# Dronmarket_Controller.net
KiCad netlist of a schematic drawn in EasyEDA
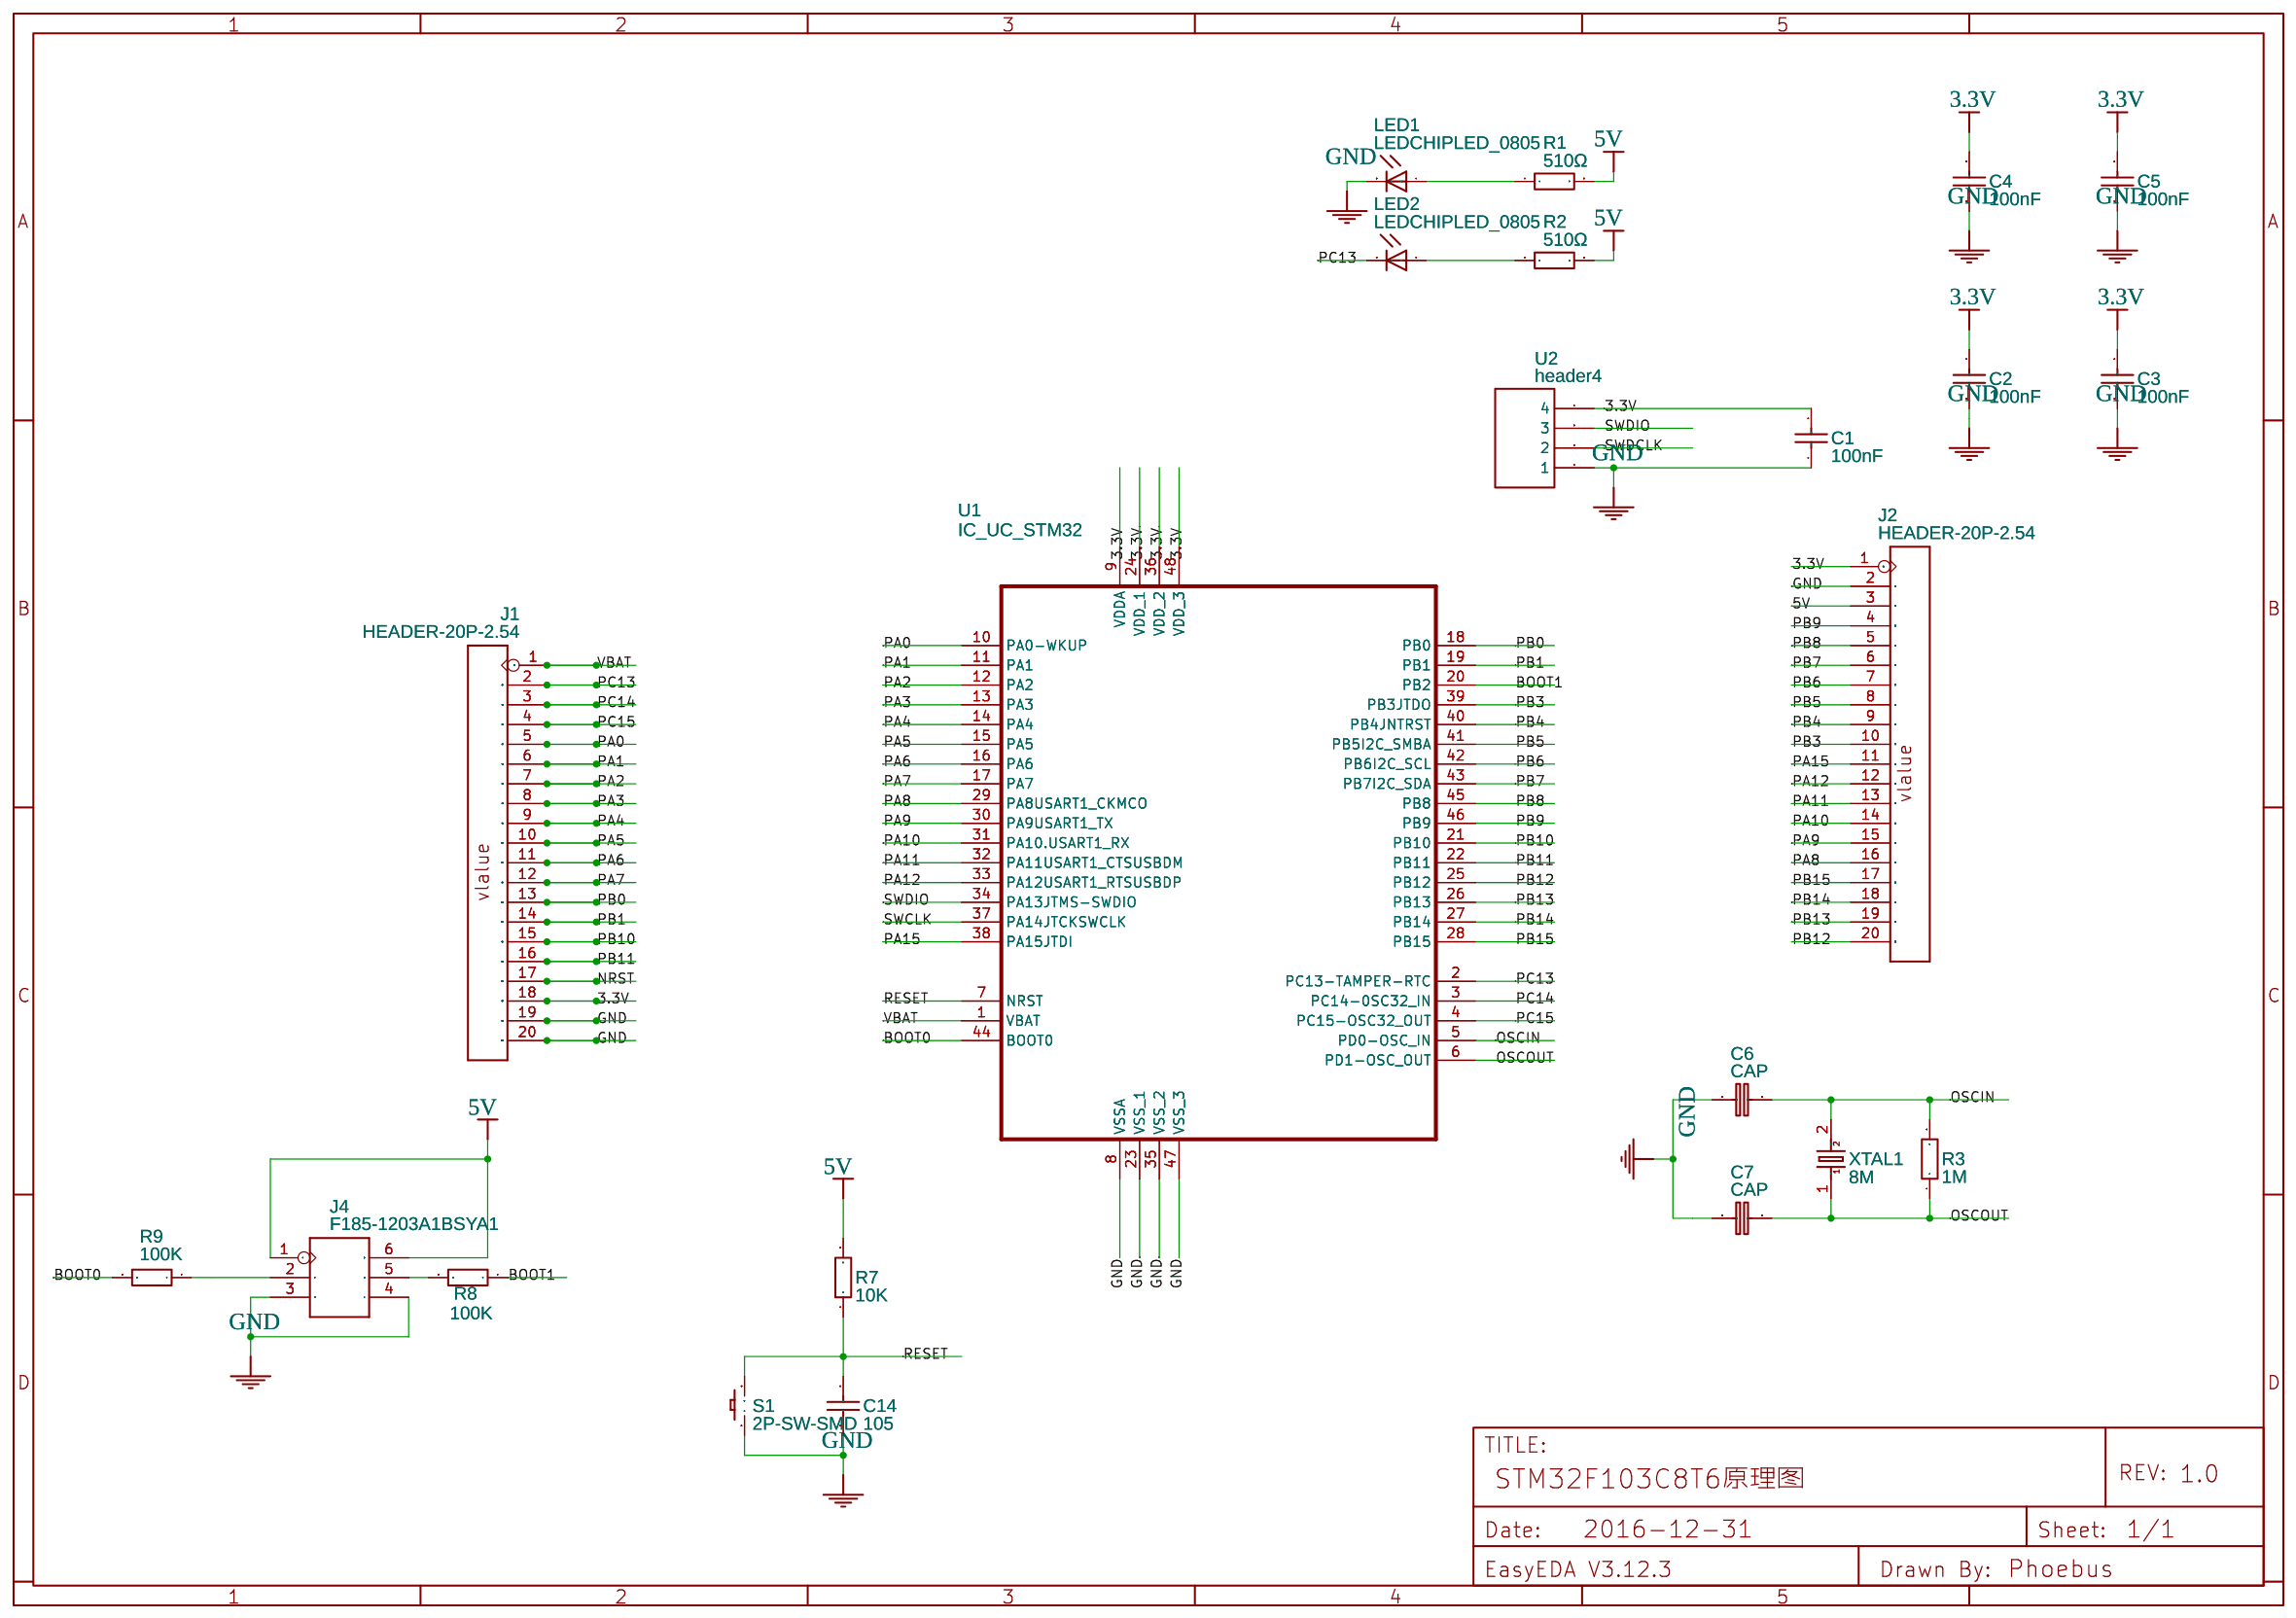
[diagram p0: Cpu Sheet]
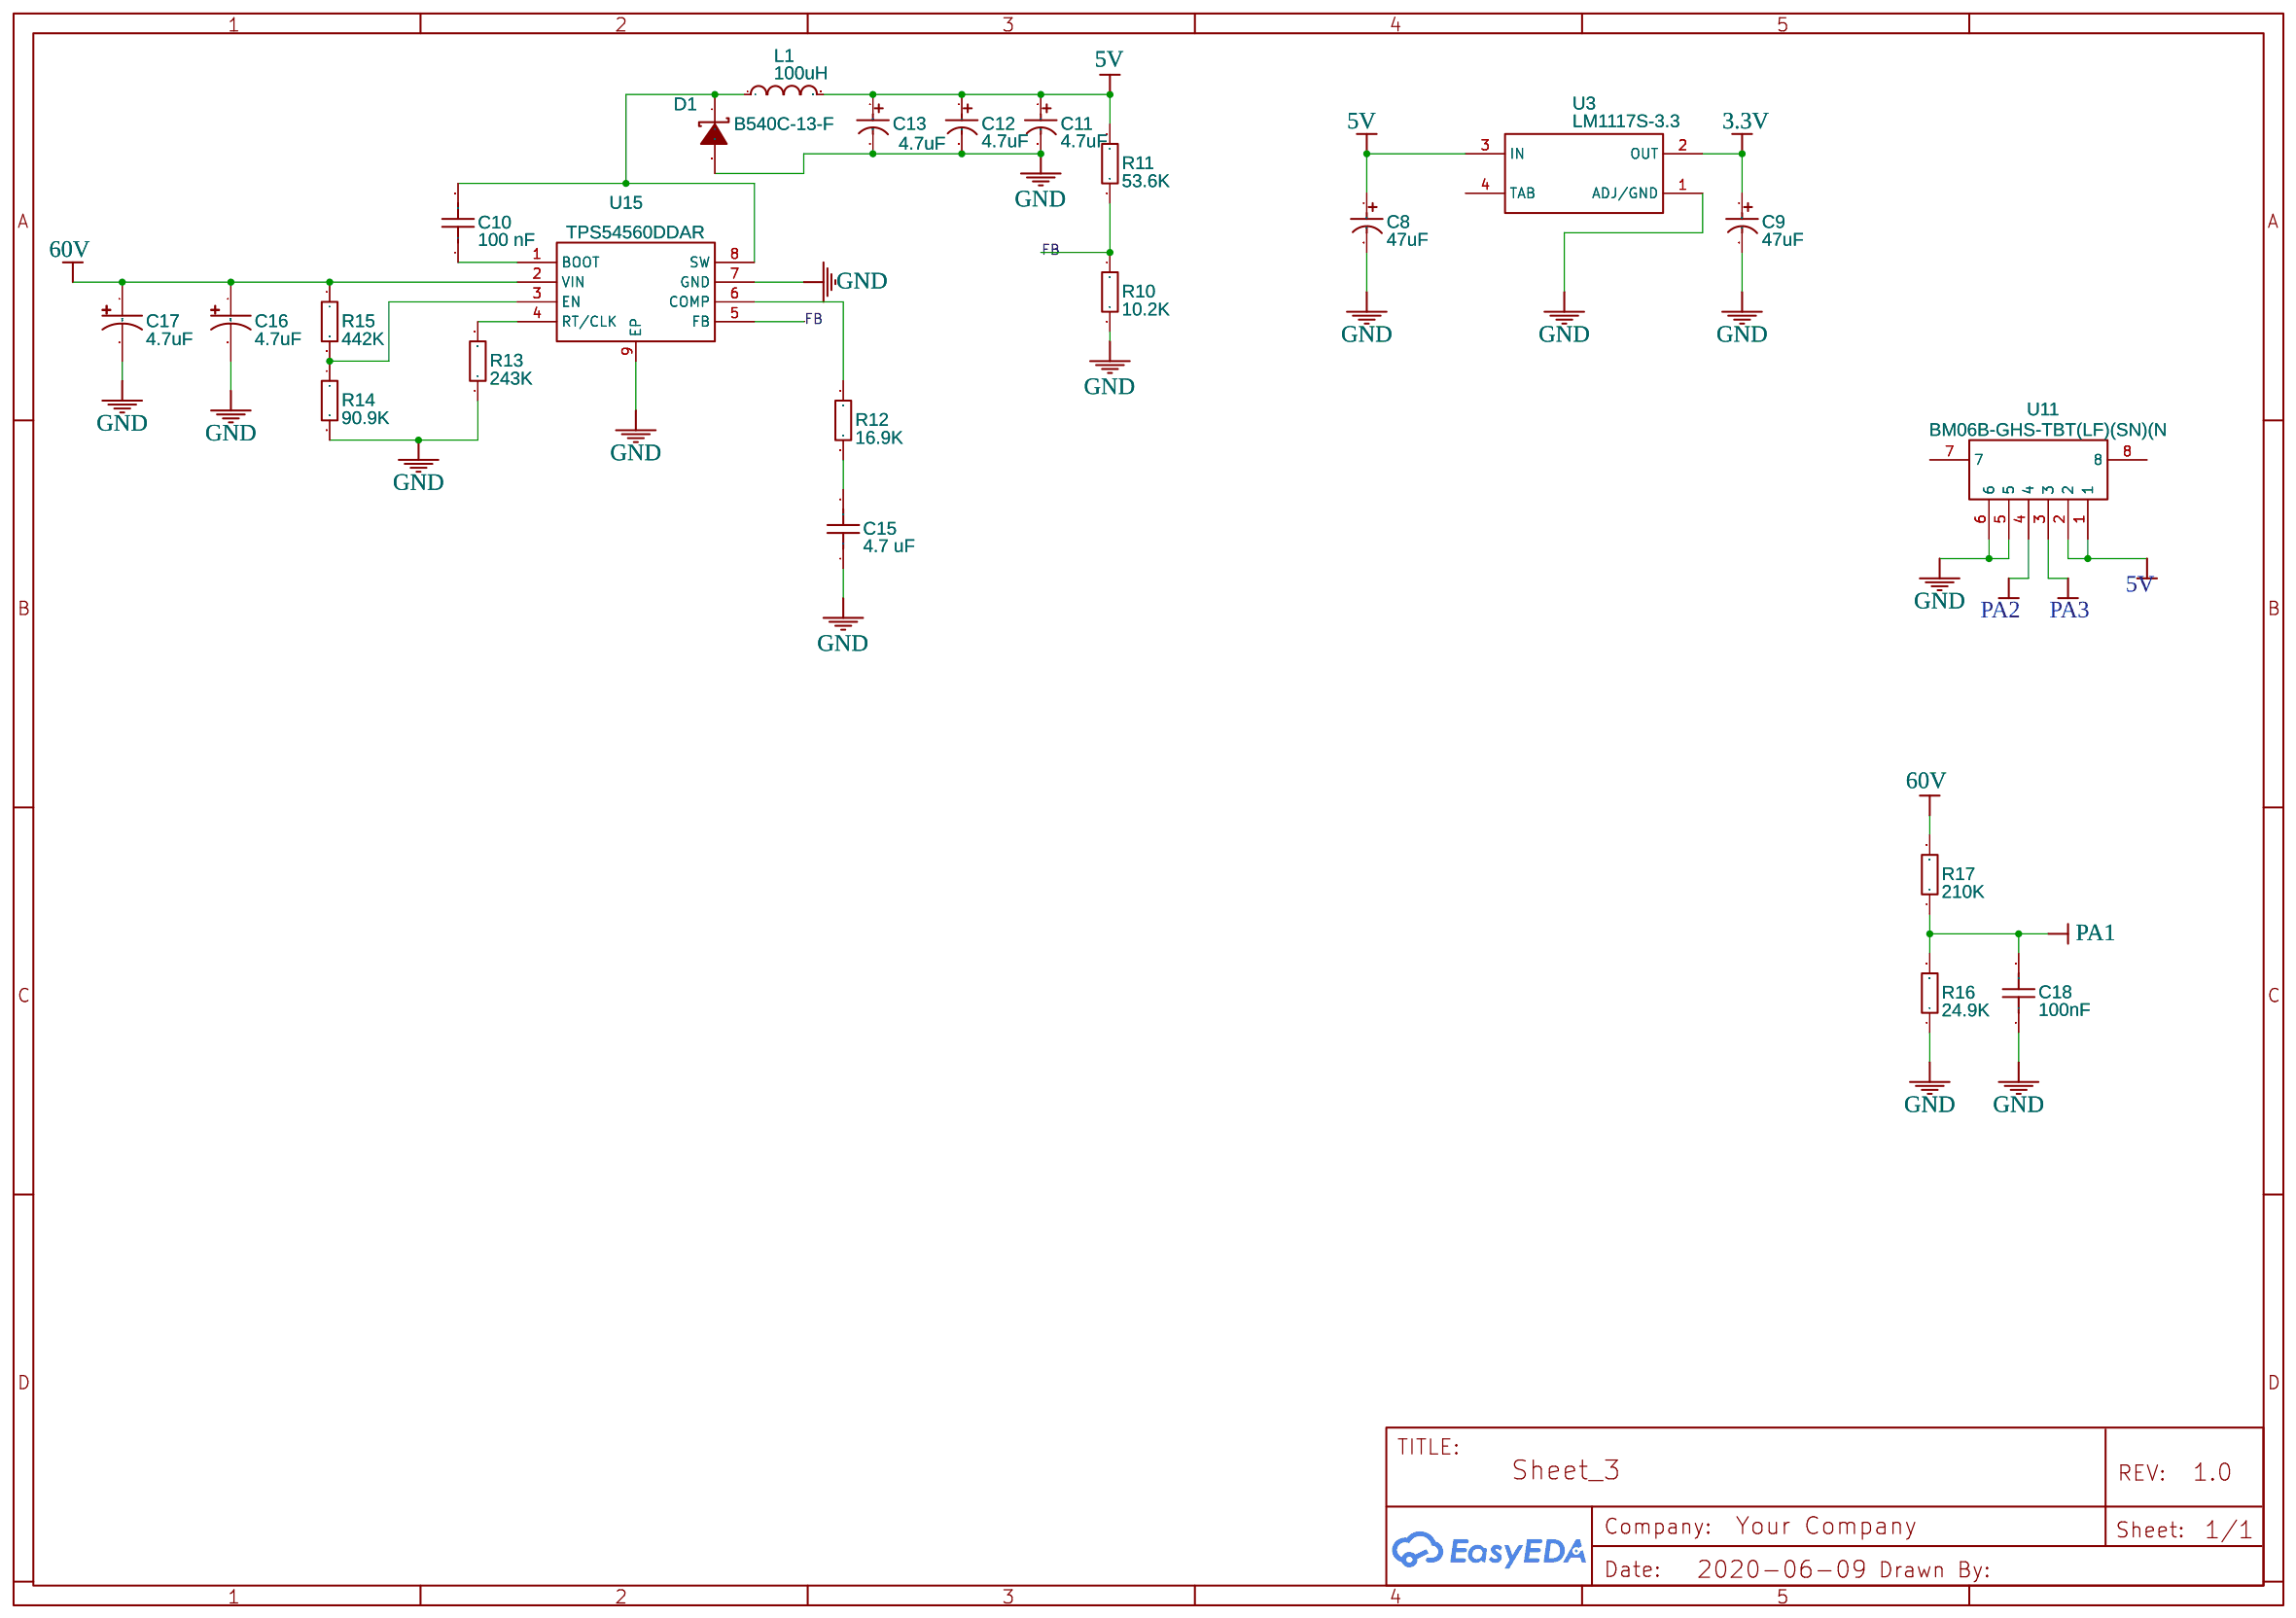
[diagram p1: Power Sheet]
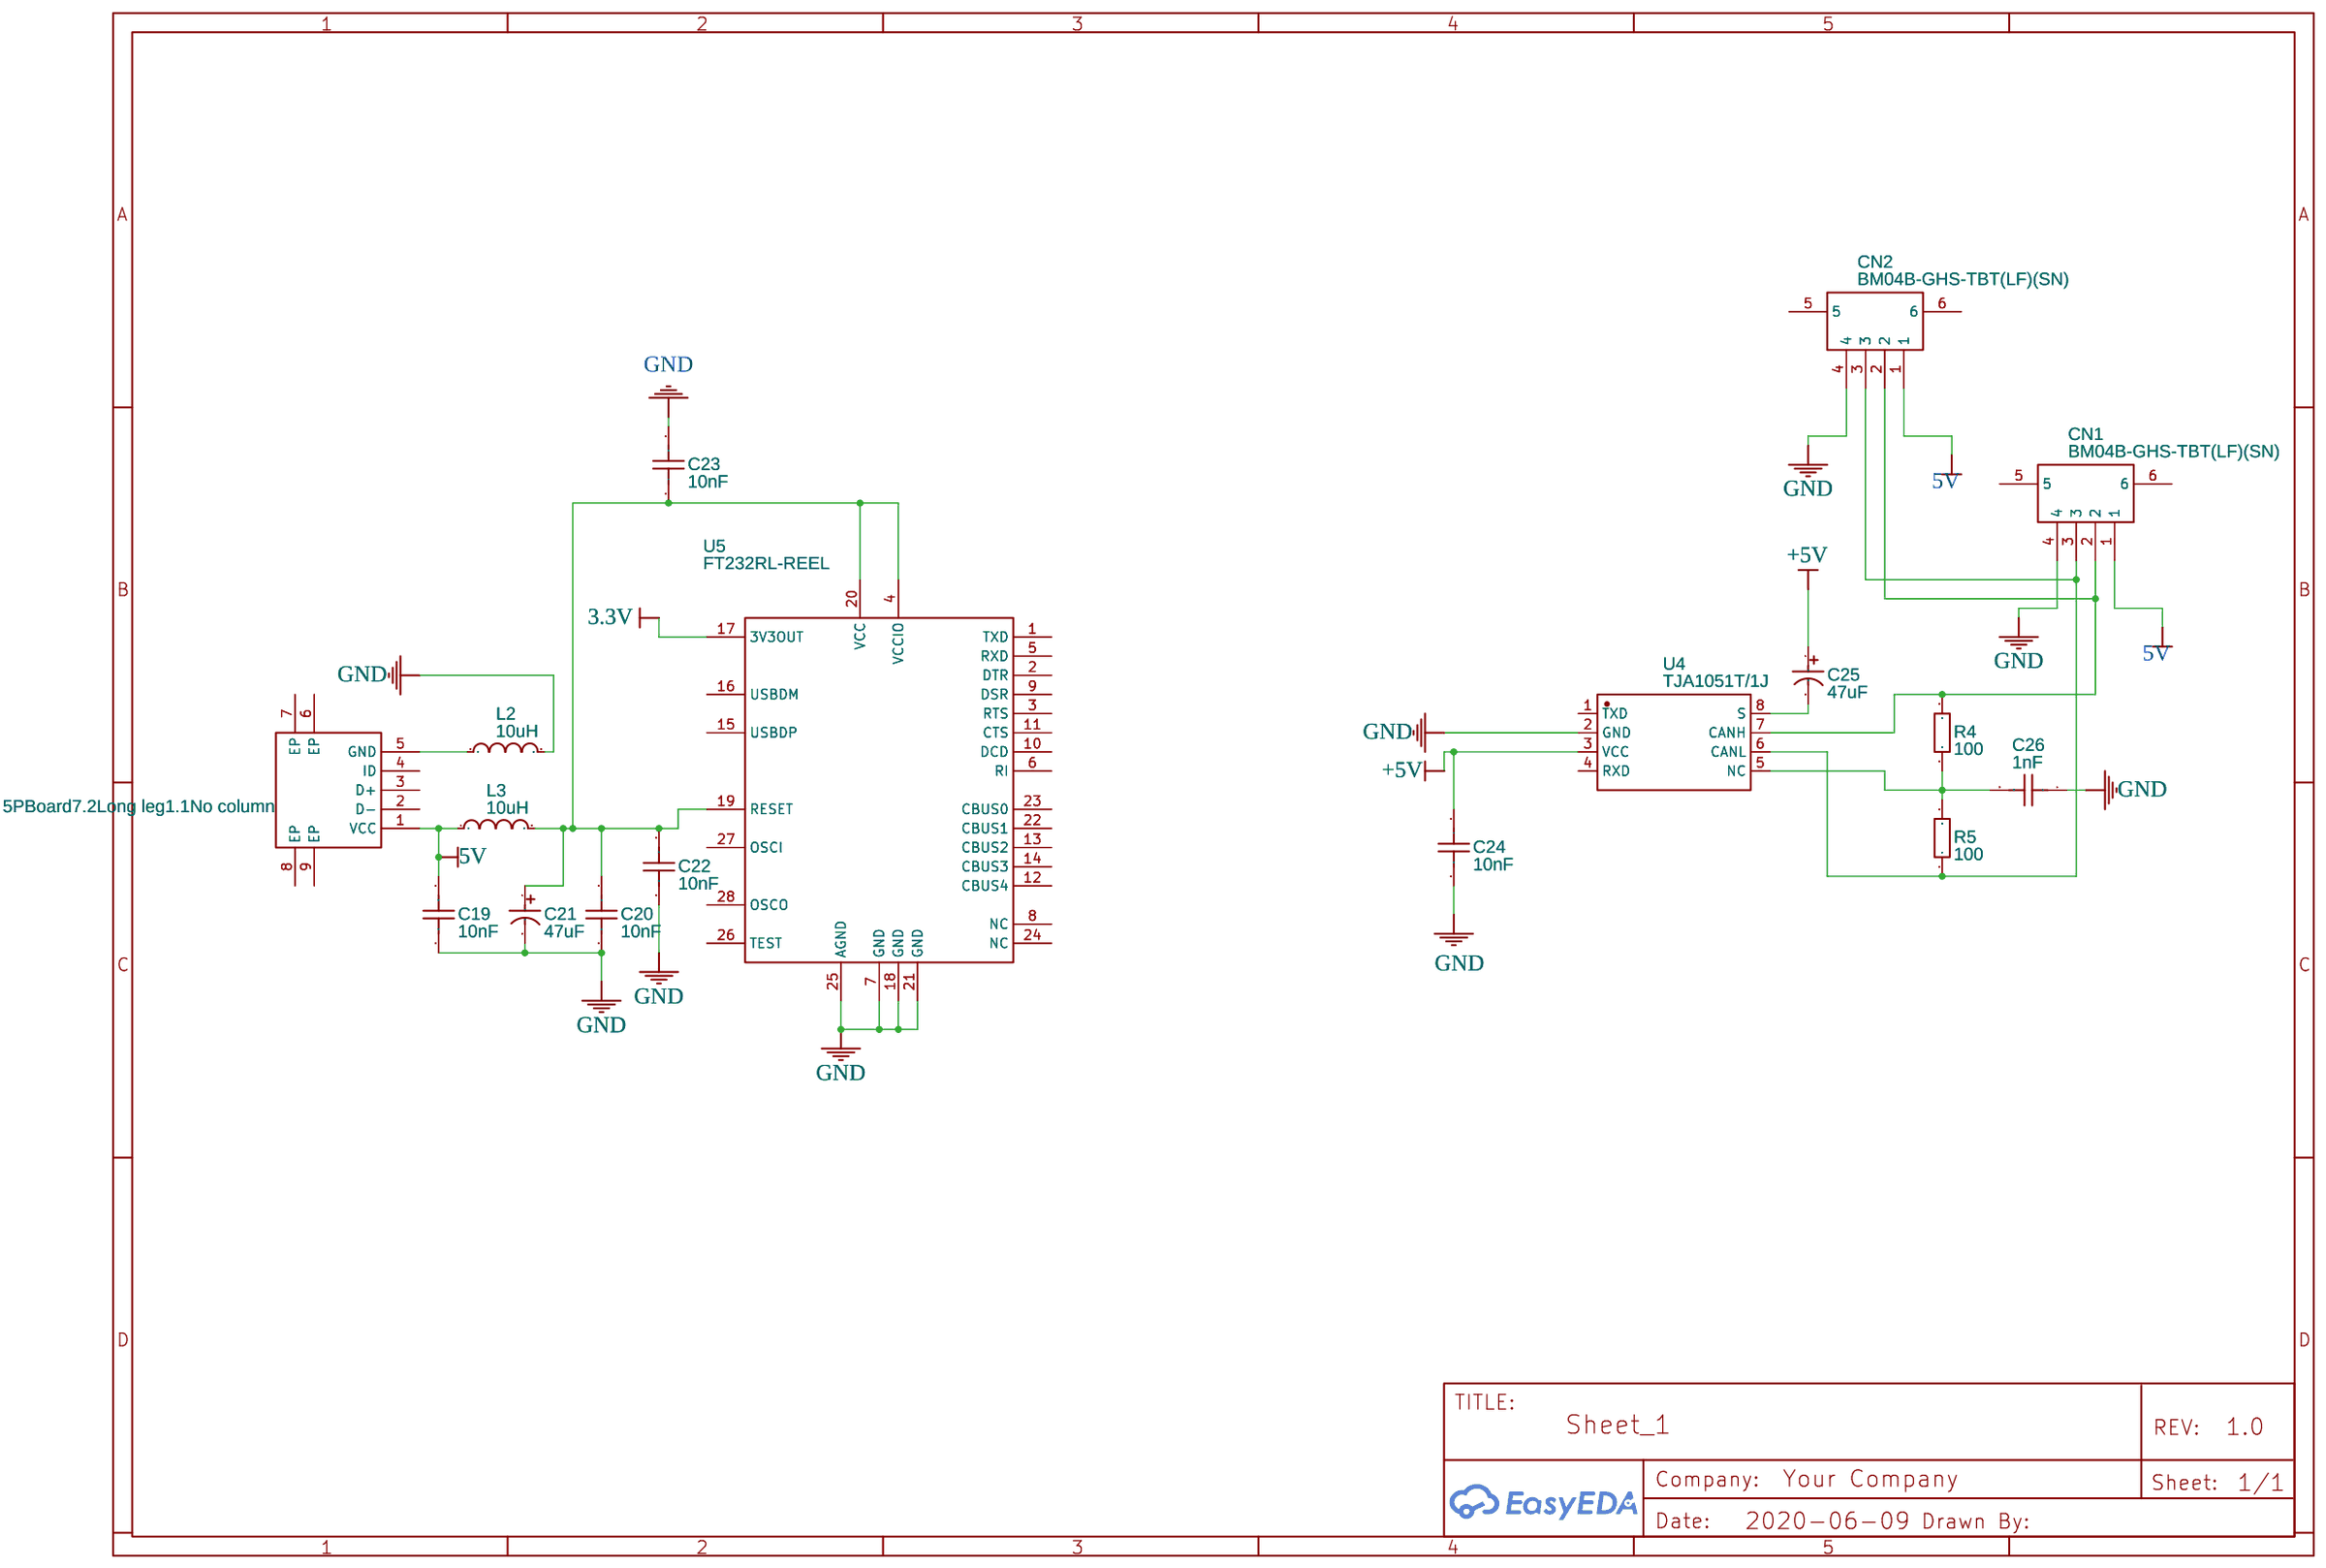
[diagram p2: Comminication Sheet]
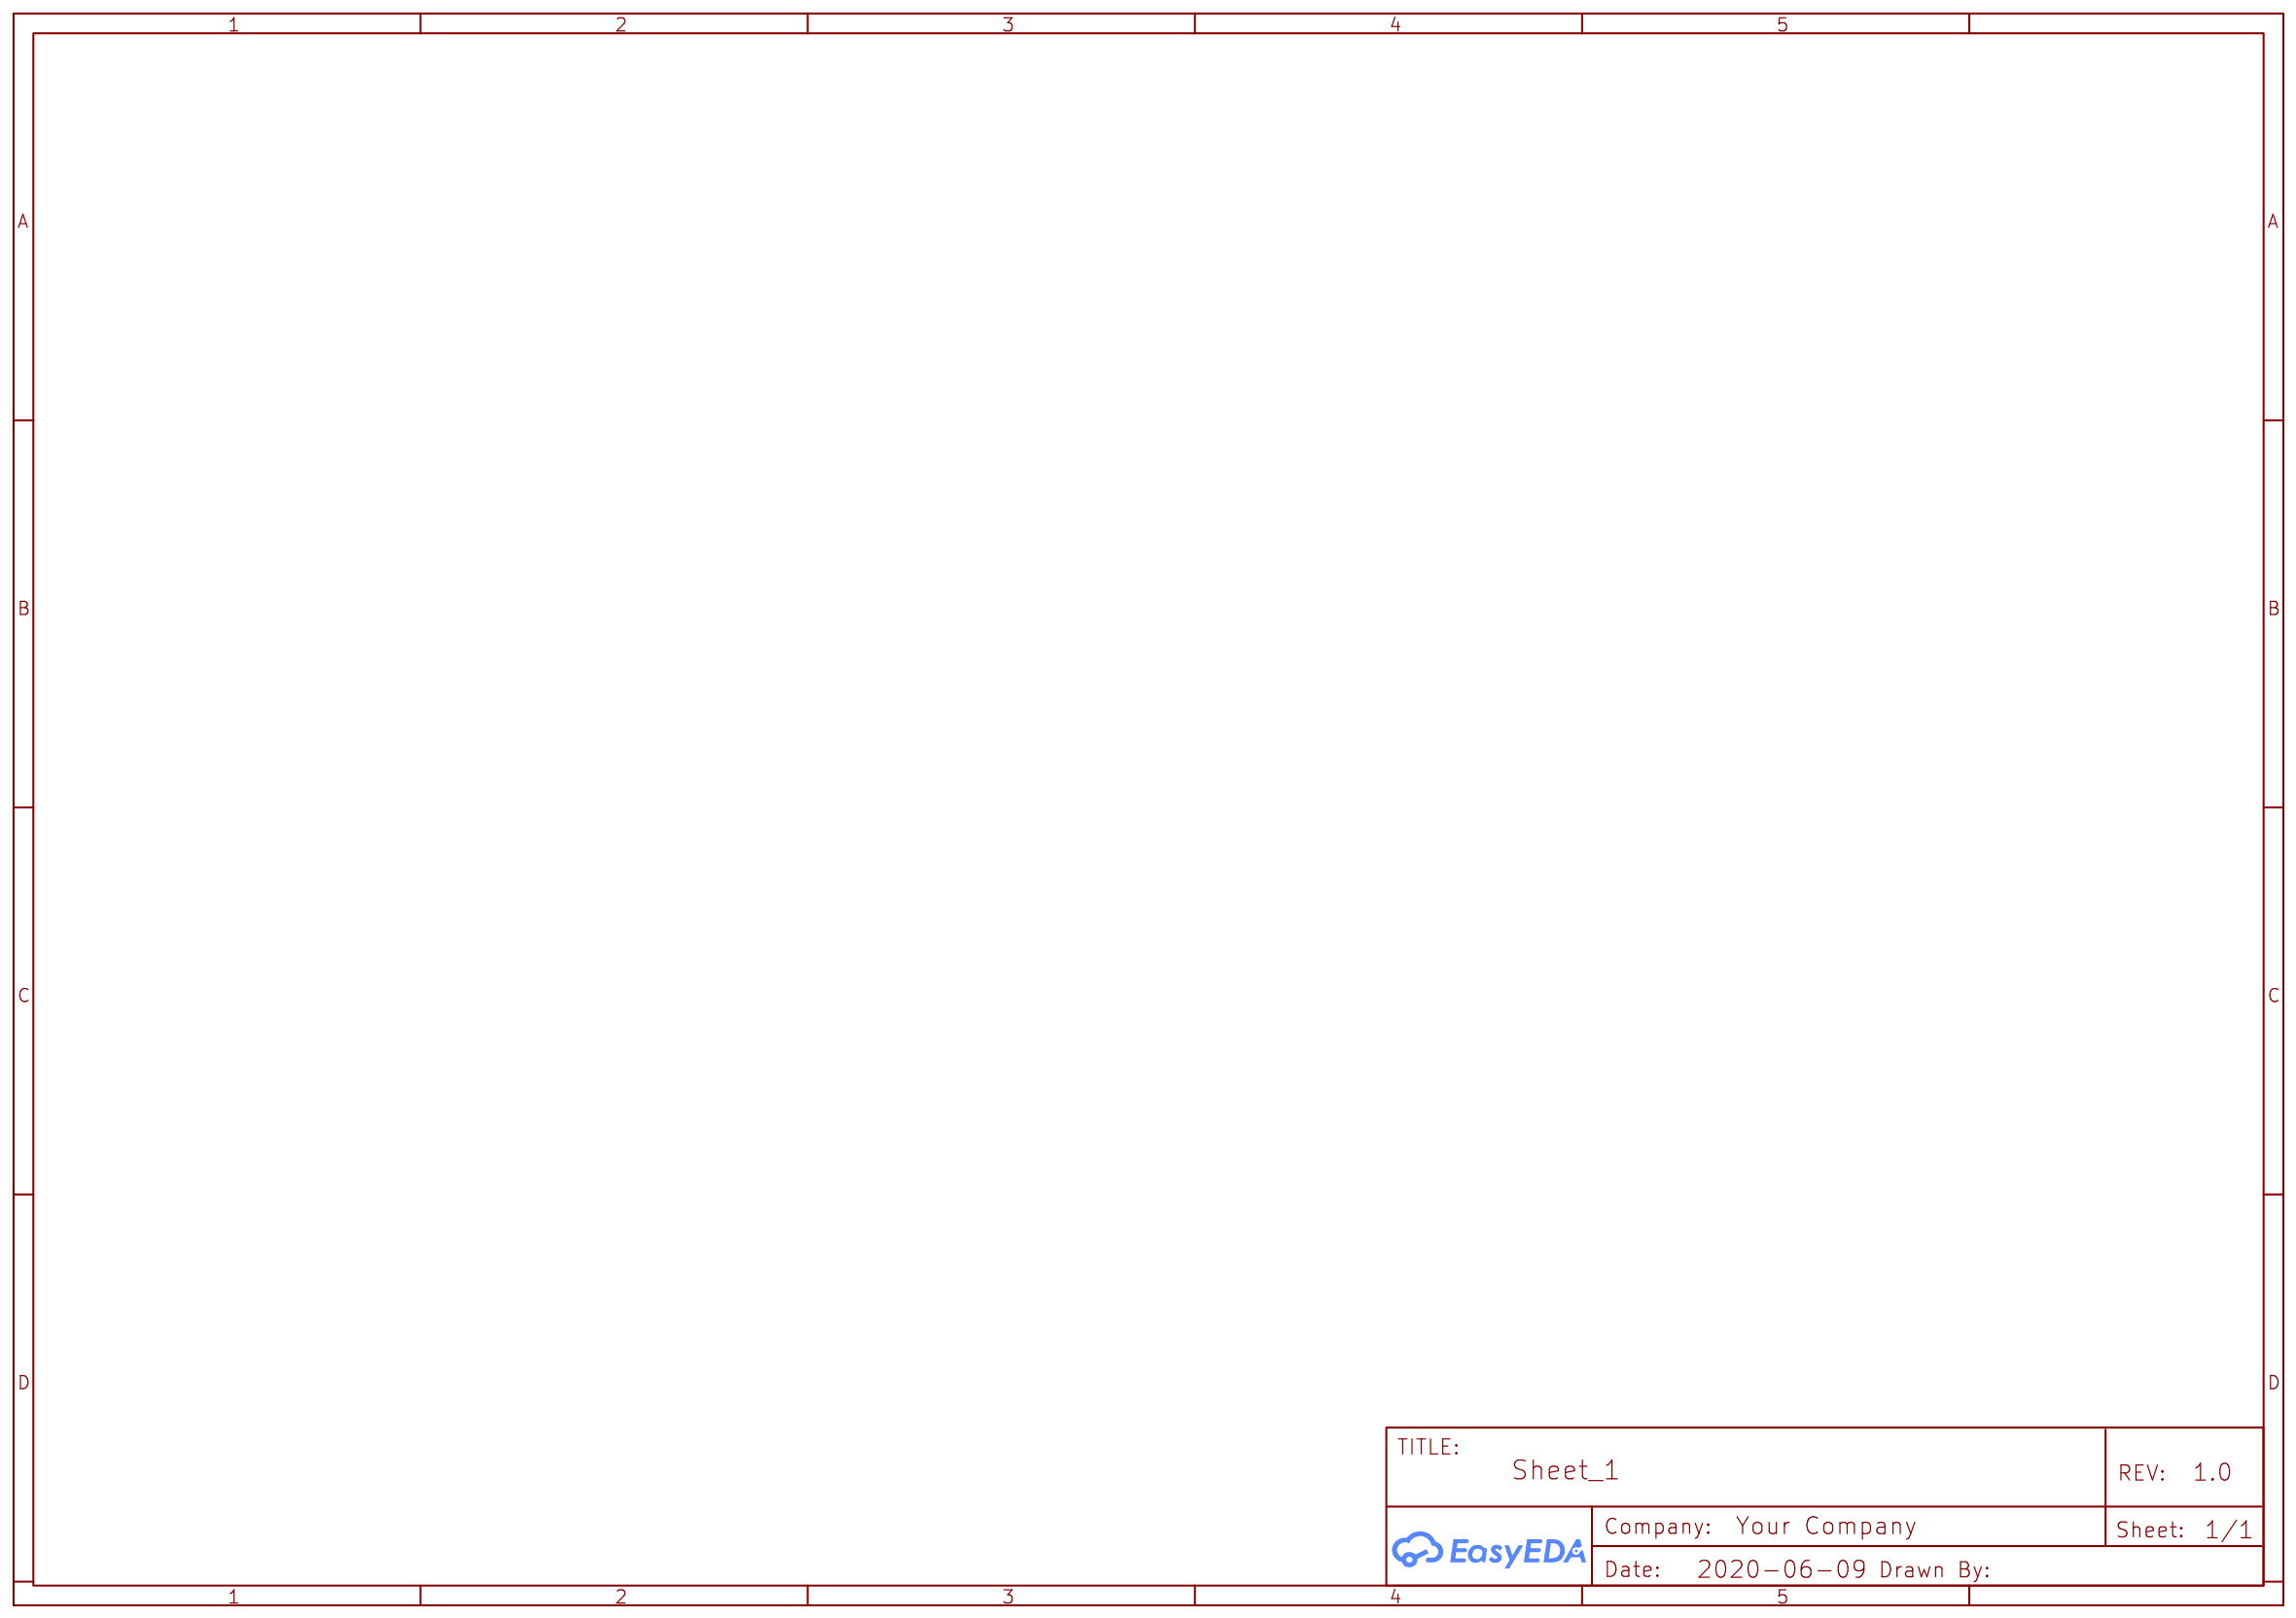
[diagram p3: Sbus&PWM]

(export (version "E")
  (design (tool "Eeschema 10.0.6"))
  (components
    (comp (ref "C1")
      (value "100nF")
      (fields
        (field (name "BOM_Manufacturer Part") "0603B104K500NT")
        (field (name "BOM_Supplier Part") "E30926")
      )
      (libsource (lib "") (part "Unknown_910_215"))
    )
    (comp (ref "C2")
      (value "100nF")
      (fields
        (field (name "BOM_Manufacturer Part") "0603B104K500NT")
        (field (name "BOM_Supplier Part") "E30926")
      )
      (libsource (lib "") (part "Unknown_990_185"))
    )
    (comp (ref "C3")
      (value "100nF")
      (fields
        (field (name "BOM_Manufacturer Part") "0603B104K500NT")
        (field (name "BOM_Supplier Part") "E30926")
      )
      (libsource (lib "") (part "Unknown_1065_185"))
    )
    (comp (ref "C4")
      (value "100nF")
      (fields
        (field (name "BOM_Manufacturer Part") "0603B104K500NT")
        (field (name "BOM_Supplier Part") "E30926")
      )
      (libsource (lib "") (part "Unknown_990_85"))
    )
    (comp (ref "C5")
      (value "100nF")
      (fields
        (field (name "BOM_Manufacturer Part") "0603B104K500NT")
        (field (name "BOM_Supplier Part") "E30926")
      )
      (libsource (lib "") (part "Unknown_1065_85"))
    )
    (comp (ref "C6")
      (value "CAP")
      (fields (field (name "BOM_Manufacturer Part") "?"))
      (libsource (lib "") (part "Unknown_880_550"))
    )
    (comp (ref "C7")
      (value "CAP")
      (fields (field (name "BOM_Manufacturer Part") "?"))
      (libsource (lib "") (part "Unknown_880_610"))
    )
    (comp (ref "C14")
      (value "105")
      (fields
        (field (name "BOM_Manufacturer Part") "0603B104K500NT")
        (field (name "BOM_Supplier Part") "E30926")
      )
      (libsource (lib "") (part "Unknown_420_705"))
    )
    (comp (ref "J1")
      (value "HEADER-20P-2.54")
      (fields (field (name "BOM_Manufacturer Part") "?"))
      (libsource (lib "") (part "Unknown_240_430"))
    )
    (comp (ref "J2")
      (value "HEADER-20P-2.54")
      (fields (field (name "BOM_Manufacturer Part") "?"))
      (libsource (lib "") (part "Unknown_960_380"))
    )
    (comp (ref "J4")
      (value "F185-1203A1BSYA1")
      (fields (field (name "BOM_Supplier Part") "320030011"))
      (libsource (lib "") (part "Unknown_170_640"))
    )
    (comp (ref "LED1")
      (value "LEDCHIPLED_0805")
      (fields (field (name "BOM_Manufacturer Part") "?"))
      (libsource (lib "") (part "Unknown_705_85"))
    )
    (comp (ref "LED2")
      (value "LEDCHIPLED_0805")
      (fields (field (name "BOM_Manufacturer Part") "?"))
      (libsource (lib "") (part "Unknown_705_125"))
    )
    (comp (ref "R1")
      (value "510Ω")
      (fields
        (field (name "BOM_Manufacturer Part") "0603WAF5100T5E")
        (field (name "BOM_Supplier Part") "E23193")
      )
      (libsource (lib "") (part "Unknown_780_85"))
    )
    (comp (ref "R2")
      (value "510Ω")
      (fields
        (field (name "BOM_Manufacturer Part") "0603WAF5100T5E")
        (field (name "BOM_Supplier Part") "E23193")
      )
      (libsource (lib "") (part "Unknown_780_125"))
    )
    (comp (ref "R3")
      (value "1M")
      (fields
        (field (name "BOM_Manufacturer Part") "0603WAF5100T5E")
        (field (name "BOM_Supplier Part") "E23193")
      )
      (libsource (lib "") (part "Unknown_970_580"))
    )
    (comp (ref "R7")
      (value "10K")
      (fields
        (field (name "BOM_Manufacturer Part") "0603WAF5100T5E")
        (field (name "BOM_Supplier Part") "E23193")
      )
      (libsource (lib "") (part "Unknown_420_640"))
    )
    (comp (ref "R8")
      (value "100K")
      (fields
        (field (name "BOM_Manufacturer Part") "0603WAF5100T5E")
        (field (name "BOM_Supplier Part") "E23193")
      )
      (libsource (lib "") (part "Unknown_230_640"))
    )
    (comp (ref "R9")
      (value "100K")
      (fields
        (field (name "BOM_Manufacturer Part") "0603WAF5100T5E")
        (field (name "BOM_Supplier Part") "E23193")
      )
      (libsource (lib "") (part "Unknown_70_640"))
    )
    (comp (ref "S1")
      (value "2P-SW-SMD")
      (fields (field (name "BOM_Manufacturer Part") "?"))
      (libsource (lib "") (part "Unknown_370_690"))
    )
    (comp (ref "U1")
      (value "IC_UC_STM32")
      (fields (field (name "BOM_Manufacturer Part") "?"))
      (libsource (lib "") (part "Unknown_570_420"))
    )
    (comp (ref "U2")
      (value "header4")
      (fields (field (name "BOM_Manufacturer Part") "?"))
      (libsource (lib "") (part "Unknown_770_220"))
    )
    (comp (ref "XTAL1")
      (value "8M")
      (fields (field (name "BOM_Manufacturer Part") "?"))
      (libsource (lib "") (part "Unknown_920_580"))
    )
    (comp (ref "C8")
      (value "47uF")
      (fields
        (field (name "BOM_Manufacturer Part") "TLJA476M010R0600")
        (field (name "BOM_Supplier Part") "C131173")
      )
      (libsource (lib "") (part "TLJA476M010R0600"))
    )
    (comp (ref "C9")
      (value "47uF")
      (fields
        (field (name "BOM_Manufacturer Part") "TLJA476M010R0600")
        (field (name "BOM_Supplier Part") "C131173")
      )
      (libsource (lib "") (part "TLJA476M010R0600"))
    )
    (comp (ref "C10")
      (value "100 nF")
      (fields
        (field (name "BOM_Manufacturer Part") "TCC0805X7R104K500DT")
        (field (name "BOM_Supplier Part") "C282732")
      )
      (libsource (lib "") (part "TCC0805X7R104K500DT"))
    )
    (comp (ref "C11")
      (value "4.7uF")
      (fields
        (field (name "BOM_Manufacturer Part") "CS1C4R7M-CRC54")
        (field (name "BOM_Supplier Part") "C116396")
      )
      (libsource (lib "") (part "CS1C4R7M-CRC54"))
    )
    (comp (ref "C12")
      (value "4.7uF")
      (fields
        (field (name "BOM_Manufacturer Part") "CS1C4R7M-CRC54")
        (field (name "BOM_Supplier Part") "C116396")
      )
      (libsource (lib "") (part "CS1C4R7M-CRC54"))
    )
    (comp (ref "C13")
      (value "4.7uF")
      (fields
        (field (name "BOM_Manufacturer Part") "CS1C4R7M-CRC54")
        (field (name "BOM_Supplier Part") "C116396")
      )
      (libsource (lib "") (part "CS1C4R7M-CRC54"))
    )
    (comp (ref "C15")
      (value "4.7 uF")
      (fields
        (field (name "BOM_Manufacturer Part") "TCC0805X7R104K500DT")
        (field (name "BOM_Supplier Part") "C282732")
      )
      (libsource (lib "") (part "TCC0805X7R104K500DT"))
    )
    (comp (ref "C16")
      (value "4.7uF")
      (fields
        (field (name "BOM_Manufacturer Part") "EEEFK1J4R7R")
        (field (name "BOM_Supplier Part") "C264058")
      )
      (libsource (lib "") (part "EEEFK1J4R7R_1"))
    )
    (comp (ref "C17")
      (value "4.7uF")
      (fields
        (field (name "BOM_Manufacturer Part") "EEEFK1J4R7R")
        (field (name "BOM_Supplier Part") "C264058")
      )
      (libsource (lib "") (part "EEEFK1J4R7R"))
    )
    (comp (ref "C18")
      (value "100nF")
      (fields
        (field (name "BOM_Manufacturer Part") "TCC0805X7R104K500DT")
        (field (name "BOM_Supplier Part") "C282732")
      )
      (libsource (lib "") (part "TCC0805X7R104K500DT"))
    )
    (comp (ref "D1")
      (value "B540C-13-F")
      (fields (field (name "BOM_Supplier Part") "C72264"))
      (libsource (lib "") (part "B540C-13-F"))
    )
    (comp (ref "L1")
      (value "100uH")
      (fields
        (field (name "BOM_Manufacturer Part") "SLH1204S101MTT")
        (field (name "BOM_Supplier Part") "C397808")
      )
      (libsource (lib "") (part "SLH1204S101MTT"))
    )
    (comp (ref "R10")
      (value "10.2K")
      (fields
        (field (name "BOM_Manufacturer Part") "RMC080510K1%N")
        (field (name "BOM_Supplier Part") "C269742")
      )
      (libsource (lib "") (part "RMC080510K1%N"))
    )
    (comp (ref "R11")
      (value "53.6K")
      (fields
        (field (name "BOM_Manufacturer Part") "RMC080510K1%N")
        (field (name "BOM_Supplier Part") "C269742")
      )
      (libsource (lib "") (part "RMC080510K1%N"))
    )
    (comp (ref "R12")
      (value "16.9K")
      (fields
        (field (name "BOM_Manufacturer Part") "RMC080510K1%N")
        (field (name "BOM_Supplier Part") "C269742")
      )
      (libsource (lib "") (part "RMC080510K1%N"))
    )
    (comp (ref "R13")
      (value "243K")
      (fields
        (field (name "BOM_Manufacturer Part") "RMC080510K1%N")
        (field (name "BOM_Supplier Part") "C269742")
      )
      (libsource (lib "") (part "RMC080510K1%N_1"))
    )
    (comp (ref "R14")
      (value "90.9K")
      (fields
        (field (name "BOM_Manufacturer Part") "RMC080510K1%N")
        (field (name "BOM_Supplier Part") "C269742")
      )
      (libsource (lib "") (part "RMC080510K1%N"))
    )
    (comp (ref "R15")
      (value "442K")
      (fields
        (field (name "BOM_Manufacturer Part") "RMC080510K1%N")
        (field (name "BOM_Supplier Part") "C269742")
      )
      (libsource (lib "") (part "RMC080510K1%N"))
    )
    (comp (ref "R16")
      (value "24.9K")
      (fields
        (field (name "BOM_Manufacturer Part") "0805W8F2492T5E")
        (field (name "BOM_Supplier Part") "C17571")
      )
      (libsource (lib "") (part "0805W8F2492T5E"))
    )
    (comp (ref "R17")
      (value "210K")
      (fields
        (field (name "BOM_Manufacturer Part") "0805W8F2103T5E")
        (field (name "BOM_Supplier Part") "C17547")
      )
      (libsource (lib "") (part "0805W8F2103T5E"))
    )
    (comp (ref "U3")
      (value "LM1117S-3.3")
      (fields (field (name "BOM_Supplier Part") "C126027"))
      (libsource (lib "") (part "LM1117S-3.3"))
    )
    (comp (ref "U11")
      (value "BM06B-GHS-TBT(LF)(SN)(N")
      (fields (field (name "BOM_Supplier Part") "C189892"))
      (libsource (lib "") (part "BM06B-GHS-TBT(LF)(SN)(N"))
    )
    (comp (ref "U15")
      (value "TPS54560DDAR")
      (fields (field (name "BOM_Supplier Part") "C31966"))
      (libsource (lib "") (part "TPS54560DDAR"))
    )
    (comp (ref "C19")
      (value "10nF")
      (fields
        (field (name "BOM_Manufacturer Part") "0805B103K500")
        (field (name "BOM_Supplier Part") "C83058")
      )
      (libsource (lib "") (part "0805B103K500"))
    )
    (comp (ref "C20")
      (value "10nF")
      (fields
        (field (name "BOM_Manufacturer Part") "0805B103K500")
        (field (name "BOM_Supplier Part") "C83058")
      )
      (libsource (lib "") (part "0805B103K500"))
    )
    (comp (ref "C21")
      (value "47uF")
      (fields
        (field (name "BOM_Manufacturer Part") "TLJA476M010R0600")
        (field (name "BOM_Supplier Part") "C131173")
      )
      (libsource (lib "") (part "TLJA476M010R0600"))
    )
    (comp (ref "C22")
      (value "10nF")
      (fields
        (field (name "BOM_Manufacturer Part") "0805B103K500")
        (field (name "BOM_Supplier Part") "C83058")
      )
      (libsource (lib "") (part "0805B103K500"))
    )
    (comp (ref "C23")
      (value "10nF")
      (fields
        (field (name "BOM_Manufacturer Part") "0805B103K500")
        (field (name "BOM_Supplier Part") "C83058")
      )
      (libsource (lib "") (part "0805B103K500"))
    )
    (comp (ref "C24")
      (value "10nF")
      (fields
        (field (name "BOM_Manufacturer Part") "0805B103K500")
        (field (name "BOM_Supplier Part") "C83058")
      )
      (libsource (lib "") (part "0805B103K500"))
    )
    (comp (ref "C25")
      (value "47uF")
      (fields
        (field (name "BOM_Manufacturer Part") "TLJA476M010R0600")
        (field (name "BOM_Supplier Part") "C131173")
      )
      (libsource (lib "") (part "TLJA476M010R0600"))
    )
    (comp (ref "C26")
      (value "1nF")
      (fields
        (field (name "BOM_Manufacturer Part") "0805B103K500")
        (field (name "BOM_Supplier Part") "C83058")
      )
      (libsource (lib "") (part "0805B103K500_1"))
    )
    (comp (ref "CN1")
      (value "BM04B-GHS-TBT(LF)(SN)")
      (fields (field (name "BOM_Supplier Part") "C161692"))
      (libsource (lib "") (part "BM04B-GHS-TBT(LF)(SN)"))
    )
    (comp (ref "CN2")
      (value "BM04B-GHS-TBT(LF)(SN)")
      (fields (field (name "BOM_Supplier Part") "C161692"))
      (libsource (lib "") (part "BM04B-GHS-TBT(LF)(SN)"))
    )
    (comp (ref "L2")
      (value "10uH")
      (fields
        (field (name "BOM_Manufacturer Part") "CI2012C100K(f)")
        (field (name "BOM_Supplier Part") "C111772")
      )
      (libsource (lib "") (part "CI2012C100K(F)"))
    )
    (comp (ref "L3")
      (value "10uH")
      (fields
        (field (name "BOM_Manufacturer Part") "CI2012C100K(f)")
        (field (name "BOM_Supplier Part") "C111772")
      )
      (libsource (lib "") (part "CI2012C100K(F)"))
    )
    (comp (ref "R4")
      (value "100")
      (fields
        (field (name "BOM_Manufacturer Part") "0805W8J0101T5E")
        (field (name "BOM_Supplier Part") "C25277")
      )
      (libsource (lib "") (part "0805W8J0101T5E"))
    )
    (comp (ref "R5")
      (value "100")
      (fields
        (field (name "BOM_Manufacturer Part") "0805W8J0101T5E")
        (field (name "BOM_Supplier Part") "C25277")
      )
      (libsource (lib "") (part "0805W8J0101T5E"))
    )
    (comp (ref "U4")
      (value "TJA1051T/1J")
      (fields (field (name "BOM_Supplier Part") "C92211"))
      (libsource (lib "") (part "TJA1051T/1J"))
    )
    (comp (ref "U5")
      (value "FT232RL-REEL")
      (fields (field (name "BOM_Supplier Part") "C8690"))
      (libsource (lib "") (part "FT232RL-REEL"))
    )
    (comp (ref "USB2")
      (value "micro 5PBoard7.2Long leg1.1No column")
      (fields (field (name "BOM_Supplier Part") "C40951"))
      (libsource (lib "") (part "micro 5PBoard7.2Long leg1.1No column"))
    )
  )
  (nets
    (net (code "1") (name "+5V") (class "Default")
      (node (ref "C24") (pin "2") (pinfunction "2_2") (pintype "unspecified"))
      (node (ref "C25") (pin "1") (pinfunction "1_1") (pintype "input"))
      (node (ref "U4") (pin "3") (pinfunction "VCC_3") (pintype "unspecified"))
    )
    (net (code "2") (name "3.3V") (class "Default")
      (node (ref "C1") (pin "2") (pinfunction "2_2") (pintype "input"))
      (node (ref "C2") (pin "2") (pinfunction "2_2") (pintype "input"))
      (node (ref "C3") (pin "2") (pinfunction "2_2") (pintype "input"))
      (node (ref "C4") (pin "2") (pinfunction "2_2") (pintype "input"))
      (node (ref "C5") (pin "2") (pinfunction "2_2") (pintype "input"))
      (node (ref "C9") (pin "1") (pinfunction "1_1") (pintype "input"))
      (node (ref "J1") (pin "18") (pinfunction "P$18_18") (pintype "unspecified"))
      (node (ref "J2") (pin "1") (pinfunction "P$1_1") (pintype "unspecified"))
      (node (ref "U1") (pin "24") (pinfunction "VDD_1_24") (pintype "passive"))
      (node (ref "U1") (pin "36") (pinfunction "VDD_2_36") (pintype "passive"))
      (node (ref "U1") (pin "48") (pinfunction "VDD_3_48") (pintype "passive"))
      (node (ref "U1") (pin "9") (pinfunction "VDDA_9") (pintype "passive"))
      (node (ref "U2") (pin "4") (pinfunction "4_4") (pintype "unspecified"))
      (node (ref "U3") (pin "2") (pinfunction "OUT_2") (pintype "passive"))
      (node (ref "U5") (pin "17") (pinfunction "3V3OUT_17") (pintype "output"))
    )
    (net (code "3") (name "5V") (class "Default")
      (node (ref "C11") (pin "1") (pinfunction "1_1") (pintype "input"))
      (node (ref "C12") (pin "1") (pinfunction "1_1") (pintype "input"))
      (node (ref "C13") (pin "1") (pinfunction "1_1") (pintype "input"))
      (node (ref "C19") (pin "2") (pinfunction "2_2") (pintype "unspecified"))
      (node (ref "C8") (pin "1") (pinfunction "1_1") (pintype "input"))
      (node (ref "CN1") (pin "1") (pinfunction "1_1") (pintype "unspecified"))
      (node (ref "CN2") (pin "1") (pinfunction "1_1") (pintype "unspecified"))
      (node (ref "J2") (pin "3") (pinfunction "P$3_3") (pintype "unspecified"))
      (node (ref "J4") (pin "1") (pinfunction "1_1") (pintype "unspecified"))
      (node (ref "J4") (pin "6") (pinfunction "6_6") (pintype "unspecified"))
      (node (ref "L1") (pin "2") (pinfunction "2_2") (pintype "unspecified"))
      (node (ref "L3") (pin "1") (pinfunction "1_1") (pintype "unspecified"))
      (node (ref "R1") (pin "2") (pinfunction "2_2") (pintype "input"))
      (node (ref "R11") (pin "1") (pinfunction "1_1") (pintype "unspecified"))
      (node (ref "R2") (pin "2") (pinfunction "2_2") (pintype "input"))
      (node (ref "R7") (pin "2") (pinfunction "2_2") (pintype "input"))
      (node (ref "U11") (pin "1") (pinfunction "1_1") (pintype "unspecified"))
      (node (ref "U11") (pin "2") (pinfunction "2_2") (pintype "unspecified"))
      (node (ref "U3") (pin "3") (pinfunction "IN_3") (pintype "passive"))
      (node (ref "USB2") (pin "1") (pinfunction "VCC_1") (pintype "unspecified"))
    )
    (net (code "4") (name "60V") (class "Default")
      (node (ref "C16") (pin "1") (pinfunction "1_1") (pintype "unspecified"))
      (node (ref "C17") (pin "1") (pinfunction "1_1") (pintype "unspecified"))
      (node (ref "R15") (pin "1") (pinfunction "1_1") (pintype "unspecified"))
      (node (ref "R17") (pin "2") (pinfunction "2_2") (pintype "input"))
      (node (ref "U15") (pin "2") (pinfunction "VIN_2") (pintype "unspecified"))
    )
    (net (code "5") (name "BOOT0") (class "Default")
      (node (ref "R9") (pin "2") (pinfunction "2_2") (pintype "input"))
      (node (ref "U1") (pin "44") (pinfunction "BOOT0_44") (pintype "unspecified"))
    )
    (net (code "6") (name "BOOT1") (class "Default")
      (node (ref "R8") (pin "1") (pinfunction "1_1") (pintype "input"))
      (node (ref "U1") (pin "20") (pinfunction "PB2_20") (pintype "unspecified"))
    )
    (net (code "7") (name "FB") (class "Default")
      (node (ref "R10") (pin "1") (pinfunction "1_1") (pintype "unspecified"))
      (node (ref "R11") (pin "2") (pinfunction "2_2") (pintype "unspecified"))
      (node (ref "U15") (pin "5") (pinfunction "FB_5") (pintype "unspecified"))
    )
    (net (code "8") (name "GND") (class "Default")
      (node (ref "C1") (pin "1") (pinfunction "1_1") (pintype "input"))
      (node (ref "C11") (pin "2") (pinfunction "2_2") (pintype "input"))
      (node (ref "C12") (pin "2") (pinfunction "2_2") (pintype "input"))
      (node (ref "C13") (pin "2") (pinfunction "2_2") (pintype "input"))
      (node (ref "C14") (pin "1") (pinfunction "1_1") (pintype "input"))
      (node (ref "C15") (pin "1") (pinfunction "1_1") (pintype "unspecified"))
      (node (ref "C16") (pin "2") (pinfunction "2_2") (pintype "unspecified"))
      (node (ref "C17") (pin "2") (pinfunction "2_2") (pintype "unspecified"))
      (node (ref "C18") (pin "1") (pinfunction "1_1") (pintype "unspecified"))
      (node (ref "C19") (pin "1") (pinfunction "1_1") (pintype "unspecified"))
      (node (ref "C2") (pin "1") (pinfunction "1_1") (pintype "input"))
      (node (ref "C20") (pin "1") (pinfunction "1_1") (pintype "unspecified"))
      (node (ref "C21") (pin "2") (pinfunction "2_2") (pintype "input"))
      (node (ref "C22") (pin "1") (pinfunction "1_1") (pintype "unspecified"))
      (node (ref "C23") (pin "2") (pinfunction "2_2") (pintype "unspecified"))
      (node (ref "C24") (pin "1") (pinfunction "1_1") (pintype "unspecified"))
      (node (ref "C26") (pin "1") (pinfunction "1_1") (pintype "unspecified"))
      (node (ref "C3") (pin "1") (pinfunction "1_1") (pintype "input"))
      (node (ref "C4") (pin "1") (pinfunction "1_1") (pintype "input"))
      (node (ref "C5") (pin "1") (pinfunction "1_1") (pintype "input"))
      (node (ref "C6") (pin "1") (pinfunction "1_1") (pintype "unspecified"))
      (node (ref "C7") (pin "1") (pinfunction "1_1") (pintype "unspecified"))
      (node (ref "C8") (pin "2") (pinfunction "2_2") (pintype "input"))
      (node (ref "C9") (pin "2") (pinfunction "2_2") (pintype "input"))
      (node (ref "CN1") (pin "4") (pinfunction "4_4") (pintype "unspecified"))
      (node (ref "CN2") (pin "4") (pinfunction "4_4") (pintype "unspecified"))
      (node (ref "D1") (pin "2") (pinfunction "A_2") (pintype "unspecified"))
      (node (ref "J1") (pin "19") (pinfunction "P$19_19") (pintype "unspecified"))
      (node (ref "J1") (pin "20") (pinfunction "P$20_20") (pintype "unspecified"))
      (node (ref "J2") (pin "2") (pinfunction "P$2_2") (pintype "unspecified"))
      (node (ref "J4") (pin "3") (pinfunction "3_3") (pintype "unspecified"))
      (node (ref "J4") (pin "4") (pinfunction "4_4") (pintype "unspecified"))
      (node (ref "L2") (pin "2") (pinfunction "2_2") (pintype "unspecified"))
      (node (ref "LED1") (pin "C") (pinfunction "C_C") (pintype "unspecified"))
      (node (ref "R10") (pin "2") (pinfunction "2_2") (pintype "unspecified"))
      (node (ref "R13") (pin "1") (pinfunction "1_1") (pintype "unspecified"))
      (node (ref "R14") (pin "2") (pinfunction "2_2") (pintype "unspecified"))
      (node (ref "R16") (pin "1") (pinfunction "1_1") (pintype "input"))
      (node (ref "S1") (pin "2") (pinfunction "1_2") (pintype "unspecified"))
      (node (ref "U1") (pin "23") (pinfunction "VSS_1_23") (pintype "unspecified"))
      (node (ref "U1") (pin "35") (pinfunction "VSS_2_35") (pintype "unspecified"))
      (node (ref "U1") (pin "47") (pinfunction "VSS_3_47") (pintype "unspecified"))
      (node (ref "U1") (pin "8") (pinfunction "VSSA_8") (pintype "unspecified"))
      (node (ref "U11") (pin "5") (pinfunction "5_5") (pintype "unspecified"))
      (node (ref "U11") (pin "6") (pinfunction "6_6") (pintype "unspecified"))
      (node (ref "U15") (pin "7") (pinfunction "GND_7") (pintype "unspecified"))
      (node (ref "U15") (pin "9") (pinfunction "EP_9") (pintype "unspecified"))
      (node (ref "U2") (pin "1") (pinfunction "1_1") (pintype "unspecified"))
      (node (ref "U3") (pin "1") (pinfunction "ADJ/GND_1") (pintype "unspecified"))
      (node (ref "U4") (pin "2") (pinfunction "GND_2") (pintype "unspecified"))
      (node (ref "U5") (pin "18") (pinfunction "GND_18") (pintype "passive"))
      (node (ref "U5") (pin "21") (pinfunction "GND_21") (pintype "passive"))
      (node (ref "U5") (pin "25") (pinfunction "AGND_25") (pintype "passive"))
      (node (ref "U5") (pin "7") (pinfunction "GND_7") (pintype "passive"))
    )
    (net (code "9") (name "NRST") (class "Default")
      (node (ref "J1") (pin "17") (pinfunction "P$17_17") (pintype "unspecified"))
    )
    (net (code "10") (name "Net-(C15-Pad2)") (class "Default")
      (node (ref "C15") (pin "2") (pinfunction "2_2") (pintype "unspecified"))
      (node (ref "R12") (pin "2") (pinfunction "2_2") (pintype "unspecified"))
    )
    (net (code "11") (name "Net-(D1-K)") (class "Default")
      (node (ref "C10") (pin "2") (pinfunction "2_2") (pintype "unspecified"))
      (node (ref "D1") (pin "1") (pinfunction "K_1") (pintype "unspecified"))
      (node (ref "L1") (pin "1") (pinfunction "1_1") (pintype "unspecified"))
      (node (ref "U15") (pin "8") (pinfunction "SW_8") (pintype "unspecified"))
    )
    (net (code "12") (name "Net-(J4-Pad2)") (class "Default")
      (node (ref "J4") (pin "2") (pinfunction "2_2") (pintype "unspecified"))
      (node (ref "R9") (pin "1") (pinfunction "1_1") (pintype "input"))
    )
    (net (code "13") (name "Net-(J4-Pad5)") (class "Default")
      (node (ref "J4") (pin "5") (pinfunction "5_5") (pintype "unspecified"))
      (node (ref "R8") (pin "2") (pinfunction "2_2") (pintype "input"))
    )
    (net (code "14") (name "Net-(LED1-PadA)") (class "Default")
      (node (ref "LED1") (pin "A") (pinfunction "A_A") (pintype "unspecified"))
      (node (ref "R1") (pin "1") (pinfunction "1_1") (pintype "input"))
    )
    (net (code "15") (name "Net-(LED2-PadA)") (class "Default")
      (node (ref "LED2") (pin "A") (pinfunction "A_A") (pintype "unspecified"))
      (node (ref "R2") (pin "1") (pinfunction "1_1") (pintype "input"))
    )
    (net (code "16") (name "Net-(U4-CANH)") (class "Default")
      (node (ref "CN1") (pin "2") (pinfunction "2_2") (pintype "unspecified"))
      (node (ref "CN2") (pin "2") (pinfunction "2_2") (pintype "unspecified"))
      (node (ref "R4") (pin "2") (pinfunction "2_2") (pintype "input"))
      (node (ref "U4") (pin "7") (pinfunction "CANH_7") (pintype "unspecified"))
    )
    (net (code "17") (name "Net-(U4-CANL)") (class "Default")
      (node (ref "CN1") (pin "3") (pinfunction "3_3") (pintype "unspecified"))
      (node (ref "CN2") (pin "3") (pinfunction "3_3") (pintype "unspecified"))
      (node (ref "R5") (pin "1") (pinfunction "1_1") (pintype "input"))
      (node (ref "U4") (pin "6") (pinfunction "CANL_6") (pintype "unspecified"))
    )
    (net (code "18") (name "Net-(U4-NC)") (class "Default")
      (node (ref "C26") (pin "2") (pinfunction "2_2") (pintype "unspecified"))
      (node (ref "R4") (pin "1") (pinfunction "1_1") (pintype "input"))
      (node (ref "R5") (pin "2") (pinfunction "2_2") (pintype "input"))
      (node (ref "U4") (pin "5") (pinfunction "NC_5") (pintype "unspecified"))
    )
    (net (code "19") (name "Net-(U4-S)") (class "Default")
      (node (ref "C25") (pin "2") (pinfunction "2_2") (pintype "input"))
      (node (ref "U4") (pin "8") (pinfunction "S_8") (pintype "unspecified"))
    )
    (net (code "20") (name "Net-(U5-RESET)") (class "Default")
      (node (ref "C20") (pin "2") (pinfunction "2_2") (pintype "unspecified"))
      (node (ref "C21") (pin "1") (pinfunction "1_1") (pintype "input"))
      (node (ref "C22") (pin "2") (pinfunction "2_2") (pintype "unspecified"))
      (node (ref "C23") (pin "1") (pinfunction "1_1") (pintype "unspecified"))
      (node (ref "L3") (pin "2") (pinfunction "2_2") (pintype "unspecified"))
      (node (ref "U5") (pin "19") (pinfunction "RESET_19") (pintype "unspecified"))
      (node (ref "U5") (pin "20") (pinfunction "VCC_20") (pintype "passive"))
      (node (ref "U5") (pin "4") (pinfunction "VCCIO_4") (pintype "passive"))
    )
    (net (code "21") (name "Net-(U15-BOOT)") (class "Default")
      (node (ref "C10") (pin "1") (pinfunction "1_1") (pintype "unspecified"))
      (node (ref "U15") (pin "1") (pinfunction "BOOT_1") (pintype "unspecified"))
    )
    (net (code "22") (name "Net-(U15-COMP)") (class "Default")
      (node (ref "R12") (pin "1") (pinfunction "1_1") (pintype "unspecified"))
      (node (ref "U15") (pin "6") (pinfunction "COMP_6") (pintype "unspecified"))
    )
    (net (code "23") (name "Net-(U15-EN)") (class "Default")
      (node (ref "R14") (pin "1") (pinfunction "1_1") (pintype "unspecified"))
      (node (ref "R15") (pin "2") (pinfunction "2_2") (pintype "unspecified"))
      (node (ref "U15") (pin "3") (pinfunction "EN_3") (pintype "unspecified"))
    )
    (net (code "24") (name "Net-(U15-RT{slash}CLK)") (class "Default")
      (node (ref "R13") (pin "2") (pinfunction "2_2") (pintype "unspecified"))
      (node (ref "U15") (pin "4") (pinfunction "RT/CLK_4") (pintype "unspecified"))
    )
    (net (code "25") (name "Net-(USB2-GND)") (class "Default")
      (node (ref "L2") (pin "1") (pinfunction "1_1") (pintype "unspecified"))
      (node (ref "USB2") (pin "5") (pinfunction "GND_5") (pintype "unspecified"))
    )
    (net (code "26") (name "OSCIN") (class "Default")
      (node (ref "C6") (pin "2") (pinfunction "2_2") (pintype "unspecified"))
      (node (ref "R3") (pin "2") (pinfunction "2_2") (pintype "input"))
      (node (ref "U1") (pin "5") (pinfunction "PD0-OSC_IN_5") (pintype "unspecified"))
      (node (ref "XTAL1") (pin "2") (pinfunction "2_2") (pintype "unspecified"))
    )
    (net (code "27") (name "OSCOUT") (class "Default")
      (node (ref "C7") (pin "2") (pinfunction "2_2") (pintype "unspecified"))
      (node (ref "R3") (pin "1") (pinfunction "1_1") (pintype "input"))
      (node (ref "U1") (pin "6") (pinfunction "PD1-OSC_OUT_6") (pintype "unspecified"))
      (node (ref "XTAL1") (pin "1") (pinfunction "1_1") (pintype "unspecified"))
    )
    (net (code "28") (name "PA0") (class "Default")
      (node (ref "J1") (pin "5") (pinfunction "P$5_5") (pintype "unspecified"))
      (node (ref "U1") (pin "10") (pinfunction "PA0-WKUP_10") (pintype "unspecified"))
    )
    (net (code "29") (name "PA1") (class "Default")
      (node (ref "C18") (pin "2") (pinfunction "2_2") (pintype "unspecified"))
      (node (ref "J1") (pin "6") (pinfunction "P$6_6") (pintype "unspecified"))
      (node (ref "R16") (pin "2") (pinfunction "2_2") (pintype "input"))
      (node (ref "R17") (pin "1") (pinfunction "1_1") (pintype "input"))
      (node (ref "U1") (pin "11") (pinfunction "PA1_11") (pintype "unspecified"))
    )
    (net (code "30") (name "PA2") (class "Default")
      (node (ref "J1") (pin "7") (pinfunction "P$7_7") (pintype "unspecified"))
      (node (ref "U1") (pin "12") (pinfunction "PA2_12") (pintype "unspecified"))
      (node (ref "U11") (pin "4") (pinfunction "4_4") (pintype "unspecified"))
    )
    (net (code "31") (name "PA3") (class "Default")
      (node (ref "J1") (pin "8") (pinfunction "P$8_8") (pintype "unspecified"))
      (node (ref "U1") (pin "13") (pinfunction "PA3_13") (pintype "unspecified"))
      (node (ref "U11") (pin "3") (pinfunction "3_3") (pintype "unspecified"))
    )
    (net (code "32") (name "PA4") (class "Default")
      (node (ref "J1") (pin "9") (pinfunction "P$9_9") (pintype "unspecified"))
      (node (ref "U1") (pin "14") (pinfunction "PA4_14") (pintype "unspecified"))
    )
    (net (code "33") (name "PA5") (class "Default")
      (node (ref "J1") (pin "10") (pinfunction "P$10_10") (pintype "unspecified"))
      (node (ref "U1") (pin "15") (pinfunction "PA5_15") (pintype "unspecified"))
    )
    (net (code "34") (name "PA6") (class "Default")
      (node (ref "J1") (pin "11") (pinfunction "P$11_11") (pintype "unspecified"))
      (node (ref "U1") (pin "16") (pinfunction "PA6_16") (pintype "unspecified"))
    )
    (net (code "35") (name "PA7") (class "Default")
      (node (ref "J1") (pin "12") (pinfunction "P$12_12") (pintype "unspecified"))
      (node (ref "U1") (pin "17") (pinfunction "PA7_17") (pintype "unspecified"))
    )
    (net (code "36") (name "PA8") (class "Default")
      (node (ref "J2") (pin "16") (pinfunction "P$16_16") (pintype "unspecified"))
      (node (ref "U1") (pin "29") (pinfunction "PA8USART1_CKMCO_29") (pintype "unspecified"))
    )
    (net (code "37") (name "PA9") (class "Default")
      (node (ref "J2") (pin "15") (pinfunction "P$15_15") (pintype "unspecified"))
      (node (ref "U1") (pin "30") (pinfunction "PA9USART1_TX_30") (pintype "unspecified"))
    )
    (net (code "38") (name "PA10") (class "Default")
      (node (ref "J2") (pin "14") (pinfunction "P$14_14") (pintype "unspecified"))
      (node (ref "U1") (pin "31") (pinfunction "PA10.USART1_RX_31") (pintype "unspecified"))
    )
    (net (code "39") (name "PA11") (class "Default")
      (node (ref "J2") (pin "13") (pinfunction "P$13_13") (pintype "unspecified"))
      (node (ref "U1") (pin "32") (pinfunction "PA11USART1_CTSUSBDM_32") (pintype "unspecified"))
    )
    (net (code "40") (name "PA12") (class "Default")
      (node (ref "J2") (pin "12") (pinfunction "P$12_12") (pintype "unspecified"))
      (node (ref "U1") (pin "33") (pinfunction "PA12USART1_RTSUSBDP_33") (pintype "unspecified"))
    )
    (net (code "41") (name "PA15") (class "Default")
      (node (ref "J2") (pin "11") (pinfunction "P$11_11") (pintype "unspecified"))
      (node (ref "U1") (pin "38") (pinfunction "PA15JTDI_38") (pintype "unspecified"))
    )
    (net (code "42") (name "PB0") (class "Default")
      (node (ref "J1") (pin "13") (pinfunction "P$13_13") (pintype "unspecified"))
      (node (ref "U1") (pin "18") (pinfunction "PB0_18") (pintype "unspecified"))
    )
    (net (code "43") (name "PB1") (class "Default")
      (node (ref "J1") (pin "14") (pinfunction "P$14_14") (pintype "unspecified"))
      (node (ref "U1") (pin "19") (pinfunction "PB1_19") (pintype "unspecified"))
    )
    (net (code "44") (name "PB3") (class "Default")
      (node (ref "J2") (pin "10") (pinfunction "P$10_10") (pintype "unspecified"))
      (node (ref "U1") (pin "39") (pinfunction "PB3JTDO_39") (pintype "unspecified"))
    )
    (net (code "45") (name "PB4") (class "Default")
      (node (ref "J2") (pin "9") (pinfunction "P$9_9") (pintype "unspecified"))
      (node (ref "U1") (pin "40") (pinfunction "PB4JNTRST_40") (pintype "unspecified"))
    )
    (net (code "46") (name "PB5") (class "Default")
      (node (ref "J2") (pin "8") (pinfunction "P$8_8") (pintype "unspecified"))
      (node (ref "U1") (pin "41") (pinfunction "PB5I2C_SMBA_41") (pintype "unspecified"))
    )
    (net (code "47") (name "PB6") (class "Default")
      (node (ref "J2") (pin "7") (pinfunction "P$7_7") (pintype "unspecified"))
      (node (ref "U1") (pin "42") (pinfunction "PB6I2C_SCL_42") (pintype "unspecified"))
    )
    (net (code "48") (name "PB7") (class "Default")
      (node (ref "J2") (pin "6") (pinfunction "P$6_6") (pintype "unspecified"))
      (node (ref "U1") (pin "43") (pinfunction "PB7I2C_SDA_43") (pintype "unspecified"))
    )
    (net (code "49") (name "PB8") (class "Default")
      (node (ref "J2") (pin "5") (pinfunction "P$5_5") (pintype "unspecified"))
      (node (ref "U1") (pin "45") (pinfunction "PB8_45") (pintype "unspecified"))
    )
    (net (code "50") (name "PB9") (class "Default")
      (node (ref "J2") (pin "4") (pinfunction "P$4_4") (pintype "unspecified"))
      (node (ref "U1") (pin "46") (pinfunction "PB9_46") (pintype "unspecified"))
    )
    (net (code "51") (name "PB10") (class "Default")
      (node (ref "J1") (pin "15") (pinfunction "P$15_15") (pintype "unspecified"))
      (node (ref "U1") (pin "21") (pinfunction "PB10_21") (pintype "unspecified"))
    )
    (net (code "52") (name "PB11") (class "Default")
      (node (ref "J1") (pin "16") (pinfunction "P$16_16") (pintype "unspecified"))
      (node (ref "U1") (pin "22") (pinfunction "PB11_22") (pintype "unspecified"))
    )
    (net (code "53") (name "PB12") (class "Default")
      (node (ref "J2") (pin "20") (pinfunction "P$20_20") (pintype "unspecified"))
      (node (ref "U1") (pin "25") (pinfunction "PB12_25") (pintype "unspecified"))
    )
    (net (code "54") (name "PB13") (class "Default")
      (node (ref "J2") (pin "19") (pinfunction "P$19_19") (pintype "unspecified"))
      (node (ref "U1") (pin "26") (pinfunction "PB13_26") (pintype "unspecified"))
    )
    (net (code "55") (name "PB14") (class "Default")
      (node (ref "J2") (pin "18") (pinfunction "P$18_18") (pintype "unspecified"))
      (node (ref "U1") (pin "27") (pinfunction "PB14_27") (pintype "unspecified"))
    )
    (net (code "56") (name "PB15") (class "Default")
      (node (ref "J2") (pin "17") (pinfunction "P$17_17") (pintype "unspecified"))
      (node (ref "U1") (pin "28") (pinfunction "PB15_28") (pintype "unspecified"))
    )
    (net (code "57") (name "PC13") (class "Default")
      (node (ref "J1") (pin "2") (pinfunction "P$2_2") (pintype "unspecified"))
      (node (ref "LED2") (pin "C") (pinfunction "C_C") (pintype "unspecified"))
      (node (ref "U1") (pin "2") (pinfunction "PC13-TAMPER-RTC_2") (pintype "unspecified"))
    )
    (net (code "58") (name "PC14") (class "Default")
      (node (ref "J1") (pin "3") (pinfunction "P$3_3") (pintype "unspecified"))
      (node (ref "U1") (pin "3") (pinfunction "PC14-0SC32_IN_3") (pintype "unspecified"))
    )
    (net (code "59") (name "PC15") (class "Default")
      (node (ref "J1") (pin "4") (pinfunction "P$4_4") (pintype "unspecified"))
      (node (ref "U1") (pin "4") (pinfunction "PC15-OSC32_OUT_4") (pintype "unspecified"))
    )
    (net (code "60") (name "RESET") (class "Default")
      (node (ref "C14") (pin "2") (pinfunction "2_2") (pintype "input"))
      (node (ref "R7") (pin "1") (pinfunction "1_1") (pintype "input"))
      (node (ref "S1") (pin "3") (pinfunction "2_3") (pintype "unspecified"))
      (node (ref "U1") (pin "7") (pinfunction "NRST_7") (pintype "unspecified"))
    )
    (net (code "61") (name "SWCLK") (class "Default")
      (node (ref "U1") (pin "37") (pinfunction "PA14JTCKSWCLK_37") (pintype "unspecified"))
    )
    (net (code "62") (name "SWDCLK") (class "Default")
      (node (ref "U2") (pin "2") (pinfunction "2_2") (pintype "unspecified"))
    )
    (net (code "63") (name "SWDIO") (class "Default")
      (node (ref "U1") (pin "34") (pinfunction "PA13JTMS-SWDIO_34") (pintype "unspecified"))
      (node (ref "U2") (pin "3") (pinfunction "3_3") (pintype "unspecified"))
    )
    (net (code "64") (name "VBAT") (class "Default")
      (node (ref "J1") (pin "1") (pinfunction "P$1_1") (pintype "unspecified"))
      (node (ref "U1") (pin "1") (pinfunction "VBAT_1") (pintype "unspecified"))
    )
    (net (code "65") (name "unconnected-(CN1-Pad5)") (class "Default")
      (node (ref "CN1") (pin "5") (pinfunction "5_5") (pintype "unspecified"))
    )
    (net (code "66") (name "unconnected-(CN1-Pad6)") (class "Default")
      (node (ref "CN1") (pin "6") (pinfunction "6_6") (pintype "unspecified"))
    )
    (net (code "67") (name "unconnected-(CN2-Pad5)") (class "Default")
      (node (ref "CN2") (pin "5") (pinfunction "5_5") (pintype "unspecified"))
    )
    (net (code "68") (name "unconnected-(CN2-Pad6)") (class "Default")
      (node (ref "CN2") (pin "6") (pinfunction "6_6") (pintype "unspecified"))
    )
    (net (code "69") (name "unconnected-(U3-TAB-Pad4)") (class "Default")
      (node (ref "U3") (pin "4") (pinfunction "TAB_4") (pintype "passive"))
    )
    (net (code "70") (name "unconnected-(U4-RXD-Pad4)") (class "Default")
      (node (ref "U4") (pin "4") (pinfunction "RXD_4") (pintype "unspecified"))
    )
    (net (code "71") (name "unconnected-(U4-TXD-Pad1)") (class "Default")
      (node (ref "U4") (pin "1") (pinfunction "TXD_1") (pintype "unspecified"))
    )
    (net (code "72") (name "unconnected-(U5-CBUS0-Pad23)") (class "Default")
      (node (ref "U5") (pin "23") (pinfunction "CBUS0_23") (pintype "bidirectional"))
    )
    (net (code "73") (name "unconnected-(U5-CBUS1-Pad22)") (class "Default")
      (node (ref "U5") (pin "22") (pinfunction "CBUS1_22") (pintype "bidirectional"))
    )
    (net (code "74") (name "unconnected-(U5-CBUS2-Pad13)") (class "Default")
      (node (ref "U5") (pin "13") (pinfunction "CBUS2_13") (pintype "bidirectional"))
    )
    (net (code "75") (name "unconnected-(U5-CBUS3-Pad14)") (class "Default")
      (node (ref "U5") (pin "14") (pinfunction "CBUS3_14") (pintype "bidirectional"))
    )
    (net (code "76") (name "unconnected-(U5-CBUS4-Pad12)") (class "Default")
      (node (ref "U5") (pin "12") (pinfunction "CBUS4_12") (pintype "bidirectional"))
    )
    (net (code "77") (name "unconnected-(U5-CTS-Pad11)") (class "Default")
      (node (ref "U5") (pin "11") (pinfunction "CTS_11") (pintype "unspecified"))
    )
    (net (code "78") (name "unconnected-(U5-DCD-Pad10)") (class "Default")
      (node (ref "U5") (pin "10") (pinfunction "DCD_10") (pintype "unspecified"))
    )
    (net (code "79") (name "unconnected-(U5-DSR-Pad9)") (class "Default")
      (node (ref "U5") (pin "9") (pinfunction "DSR_9") (pintype "unspecified"))
    )
    (net (code "80") (name "unconnected-(U5-DTR-Pad2)") (class "Default")
      (node (ref "U5") (pin "2") (pinfunction "DTR_2") (pintype "output"))
    )
    (net (code "81") (name "unconnected-(U5-NC-Pad8)") (class "Default")
      (node (ref "U5") (pin "8") (pinfunction "NC_8") (pintype "unspecified"))
    )
    (net (code "82") (name "unconnected-(U5-NC-Pad24)") (class "Default")
      (node (ref "U5") (pin "24") (pinfunction "NC_24") (pintype "unspecified"))
    )
    (net (code "83") (name "unconnected-(U5-OSCI-Pad27)") (class "Default")
      (node (ref "U5") (pin "27") (pinfunction "OSCI_27") (pintype "unspecified"))
    )
    (net (code "84") (name "unconnected-(U5-OSCO-Pad28)") (class "Default")
      (node (ref "U5") (pin "28") (pinfunction "OSCO_28") (pintype "output"))
    )
    (net (code "85") (name "unconnected-(U5-RI-Pad6)") (class "Default")
      (node (ref "U5") (pin "6") (pinfunction "RI_6") (pintype "unspecified"))
    )
    (net (code "86") (name "unconnected-(U5-RTS-Pad3)") (class "Default")
      (node (ref "U5") (pin "3") (pinfunction "RTS_3") (pintype "output"))
    )
    (net (code "87") (name "unconnected-(U5-RXD-Pad5)") (class "Default")
      (node (ref "U5") (pin "5") (pinfunction "RXD_5") (pintype "unspecified"))
    )
    (net (code "88") (name "unconnected-(U5-TEST-Pad26)") (class "Default")
      (node (ref "U5") (pin "26") (pinfunction "TEST_26") (pintype "unspecified"))
    )
    (net (code "89") (name "unconnected-(U5-TXD-Pad1)") (class "Default")
      (node (ref "U5") (pin "1") (pinfunction "TXD_1") (pintype "output"))
    )
    (net (code "90") (name "unconnected-(U5-USBDM-Pad16)") (class "Default")
      (node (ref "U5") (pin "16") (pinfunction "USBDM_16") (pintype "bidirectional"))
    )
    (net (code "91") (name "unconnected-(U5-USBDP-Pad15)") (class "Default")
      (node (ref "U5") (pin "15") (pinfunction "USBDP_15") (pintype "bidirectional"))
    )
    (net (code "92") (name "unconnected-(U11-Pad7)") (class "Default")
      (node (ref "U11") (pin "7") (pinfunction "7_7") (pintype "unspecified"))
    )
    (net (code "93") (name "unconnected-(U11-Pad8)") (class "Default")
      (node (ref "U11") (pin "8") (pinfunction "8_8") (pintype "unspecified"))
    )
    (net (code "94") (name "unconnected-(USB2-D+-Pad3)") (class "Default")
      (node (ref "USB2") (pin "3") (pinfunction "D+_3") (pintype "unspecified"))
    )
    (net (code "95") (name "unconnected-(USB2-D--Pad2)") (class "Default")
      (node (ref "USB2") (pin "2") (pinfunction "D-_2") (pintype "unspecified"))
    )
    (net (code "96") (name "unconnected-(USB2-EP-Pad6)") (class "Default")
      (node (ref "USB2") (pin "6") (pinfunction "EP_6") (pintype "unspecified"))
    )
    (net (code "97") (name "unconnected-(USB2-EP-Pad7)") (class "Default")
      (node (ref "USB2") (pin "7") (pinfunction "EP_7") (pintype "unspecified"))
    )
    (net (code "98") (name "unconnected-(USB2-EP-Pad8)") (class "Default")
      (node (ref "USB2") (pin "8") (pinfunction "EP_8") (pintype "unspecified"))
    )
    (net (code "99") (name "unconnected-(USB2-EP-Pad9)") (class "Default")
      (node (ref "USB2") (pin "9") (pinfunction "EP_9") (pintype "unspecified"))
    )
    (net (code "100") (name "unconnected-(USB2-ID-Pad4)") (class "Default")
      (node (ref "USB2") (pin "4") (pinfunction "ID_4") (pintype "unspecified"))
    )
  )
)
